# 001_top.net
KiCad netlist of a schematic drawn in Altium Designer
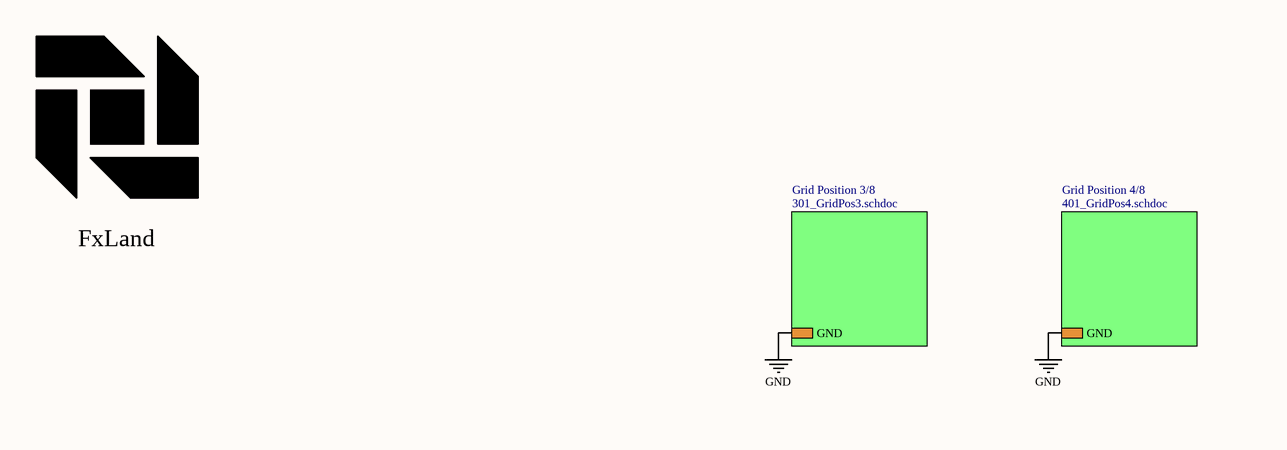
[diagram p0: 001_top.SchDoc, left]
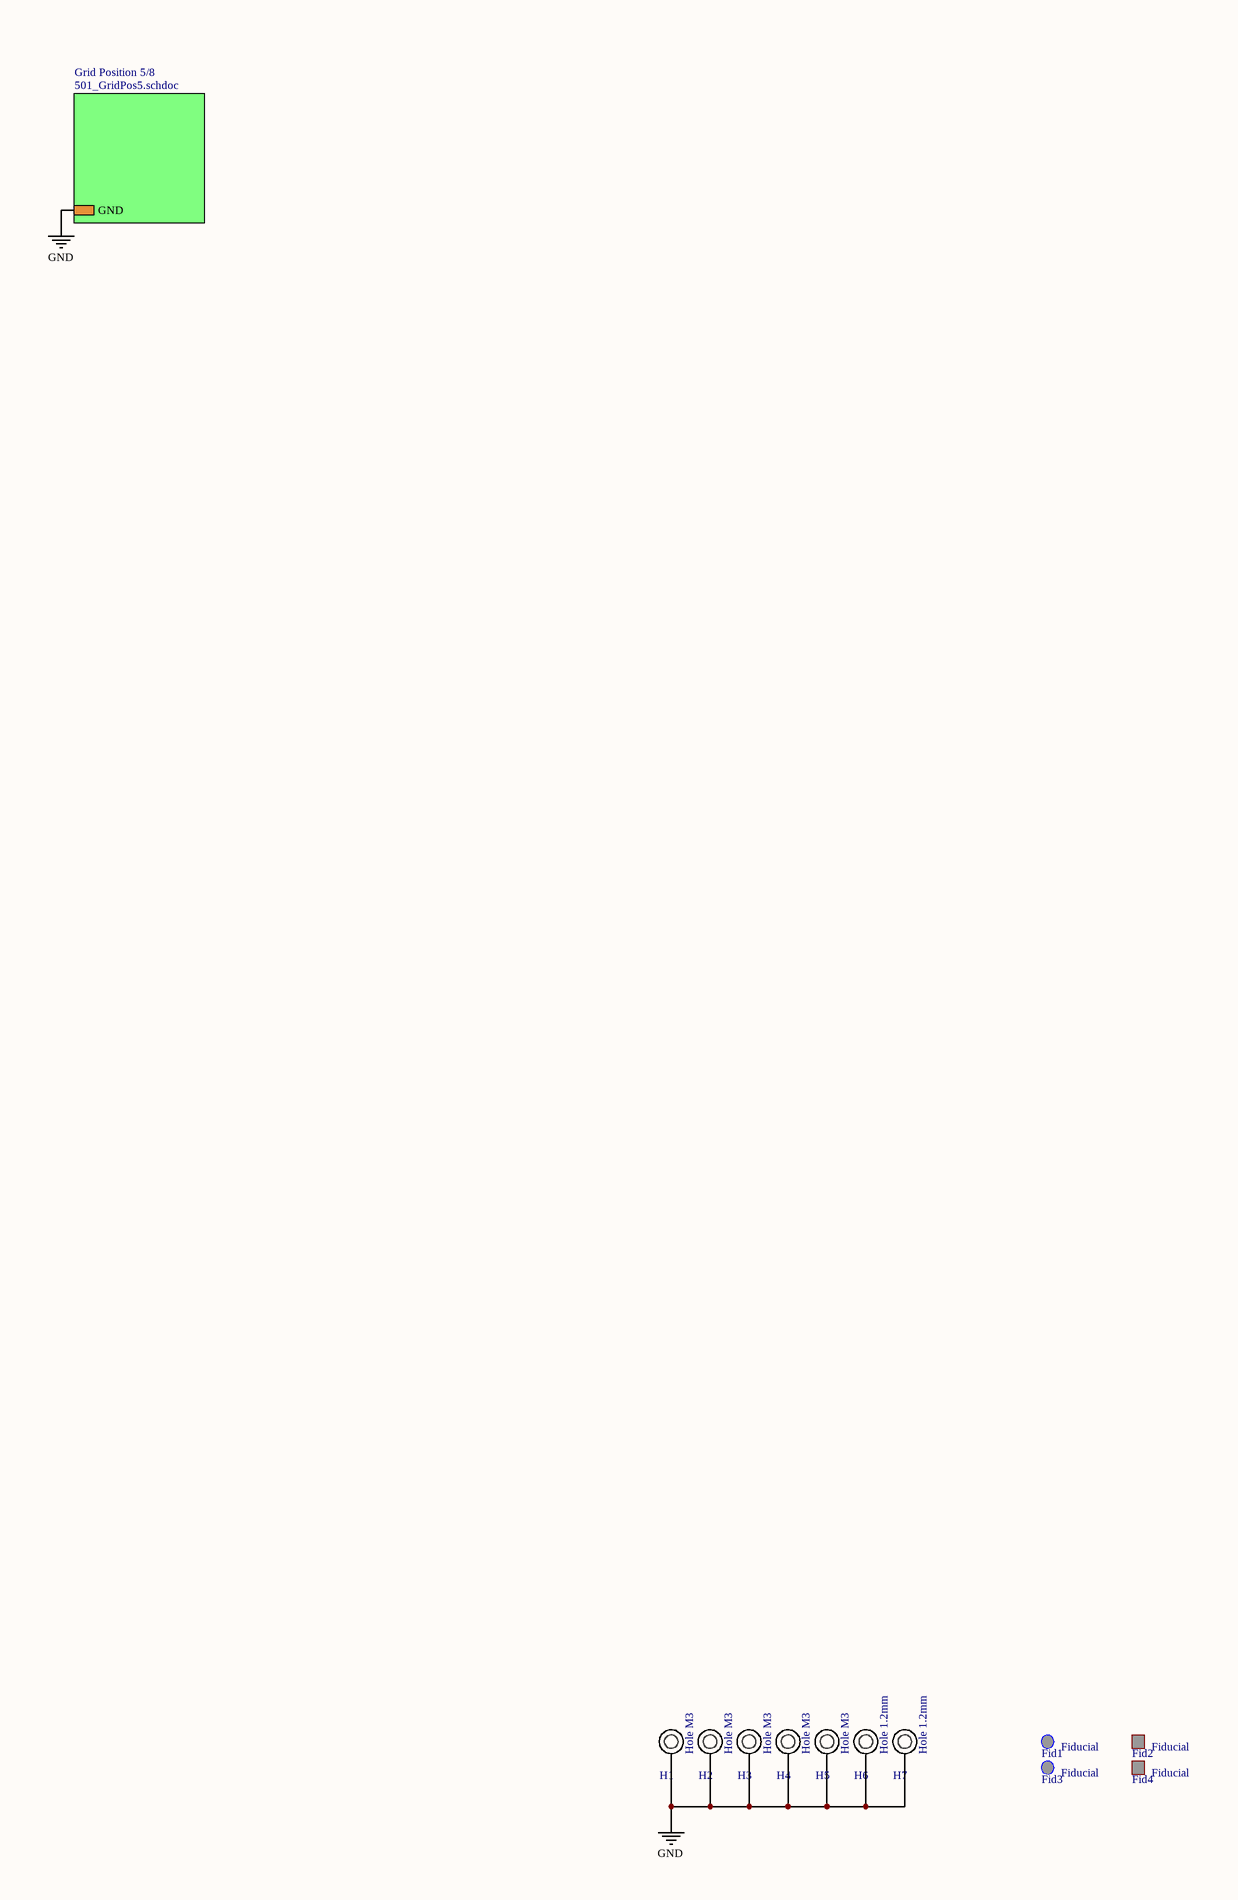
[diagram p1: 001_top.SchDoc, right]

(export (version "E")
  (design (tool "Eeschema 10.0.6"))
  (components
    (comp (ref "Fid1")
      (value "Fiducial")
      (footprint "FidR_1.0mm")
      (description "Fiducial Round 1mm")
      (fields (field (name "REFVAL") "Fiducial") (field (name "PART NUMBER") "ME0011"))
      (libsource (lib "GTS_Database") (part "FidR_1.0mm"))
    )
    (comp (ref "Fid2")
      (value "Fiducial")
      (footprint "FidS_1.0mm")
      (description "Fiducial Sqaure 1mm")
      (fields (field (name "REFVAL") "Fiducial") (field (name "PART NUMBER") "ME0012"))
      (libsource (lib "GTS_Database") (part "FidS_1.0mm"))
    )
    (comp (ref "Fid3")
      (value "Fiducial")
      (footprint "FidR_1.0mm")
      (description "Fiducial Round 1mm")
      (fields (field (name "REFVAL") "Fiducial") (field (name "PART NUMBER") "ME0011"))
      (libsource (lib "GTS_Database") (part "FidR_1.0mm"))
    )
    (comp (ref "Fid4")
      (value "Fiducial")
      (footprint "FidS_1.0mm")
      (description "Fiducial Sqaure 1mm")
      (fields (field (name "REFVAL") "Fiducial") (field (name "PART NUMBER") "ME0012"))
      (libsource (lib "GTS_Database") (part "FidS_1.0mm"))
    )
    (comp (ref "H1")
      (value "Hole M3")
      (footprint "HOLE_M3")
      (description "Mounting Hole M3")
      (fields (field (name "REFVAL") "Hole M3") (field (name "PART NUMBER") "ME0001"))
      (libsource (lib "GTS_Database") (part "HOLE"))
    )
    (comp (ref "H2")
      (value "Hole M3")
      (footprint "HOLE_M3")
      (description "Mounting Hole M3")
      (fields (field (name "REFVAL") "Hole M3") (field (name "PART NUMBER") "ME0001"))
      (libsource (lib "GTS_Database") (part "HOLE"))
    )
    (comp (ref "H3")
      (value "Hole M3")
      (footprint "HOLE_M3")
      (description "Mounting Hole M3")
      (fields (field (name "REFVAL") "Hole M3") (field (name "PART NUMBER") "ME0001"))
      (libsource (lib "GTS_Database") (part "HOLE"))
    )
    (comp (ref "H4")
      (value "Hole M3")
      (footprint "HOLE_M3")
      (description "Mounting Hole M3")
      (fields (field (name "REFVAL") "Hole M3") (field (name "PART NUMBER") "ME0001"))
      (libsource (lib "GTS_Database") (part "HOLE"))
    )
    (comp (ref "H5")
      (value "Hole M3")
      (footprint "HOLE_M3")
      (description "Mounting Hole M3")
      (fields (field (name "REFVAL") "Hole M3") (field (name "PART NUMBER") "ME0001"))
      (libsource (lib "GTS_Database") (part "HOLE"))
    )
    (comp (ref "H6")
      (value "Hole 1.2mm")
      (footprint "HOLE_1.2MM")
      (description "Mounting Hole 1.2MM")
      (fields (field (name "REFVAL") "Hole 1.2mm") (field (name "PART NUMBER") "ME0025"))
      (libsource (lib "GTS_Database") (part "HOLE"))
    )
    (comp (ref "H7")
      (value "Hole 1.2mm")
      (footprint "HOLE_1.2MM")
      (description "Mounting Hole 1.2MM")
      (fields (field (name "REFVAL") "Hole 1.2mm") (field (name "PART NUMBER") "ME0025"))
      (libsource (lib "GTS_Database") (part "HOLE"))
    )
    (comp (ref "Logo FxLand1")
      (value "FxLand")
      (footprint "Logo_FxLand_3")
      (description "Logo FxLand 3")
      (fields (field (name "PART NUMBER") "ME0008"))
      (libsource (lib "GTS_Database") (part "Logo_FxLand_2"))
    )
  )
  (nets
    (net (code "1") (name "GND") (class "Default")
      (node (ref "H1") (pin "1") (pinfunction "1_1") (pintype "passive"))
      (node (ref "H2") (pin "1") (pinfunction "1_1") (pintype "passive"))
      (node (ref "H3") (pin "1") (pinfunction "1_1") (pintype "passive"))
      (node (ref "H4") (pin "1") (pinfunction "1_1") (pintype "passive"))
      (node (ref "H5") (pin "1") (pinfunction "1_1") (pintype "passive"))
      (node (ref "H6") (pin "1") (pinfunction "1_1") (pintype "passive"))
      (node (ref "H7") (pin "1") (pinfunction "1_1") (pintype "passive"))
    )
  )
)
